# platine_clairage_voiture.net
KiCad netlist of a schematic drawn in EAGLE
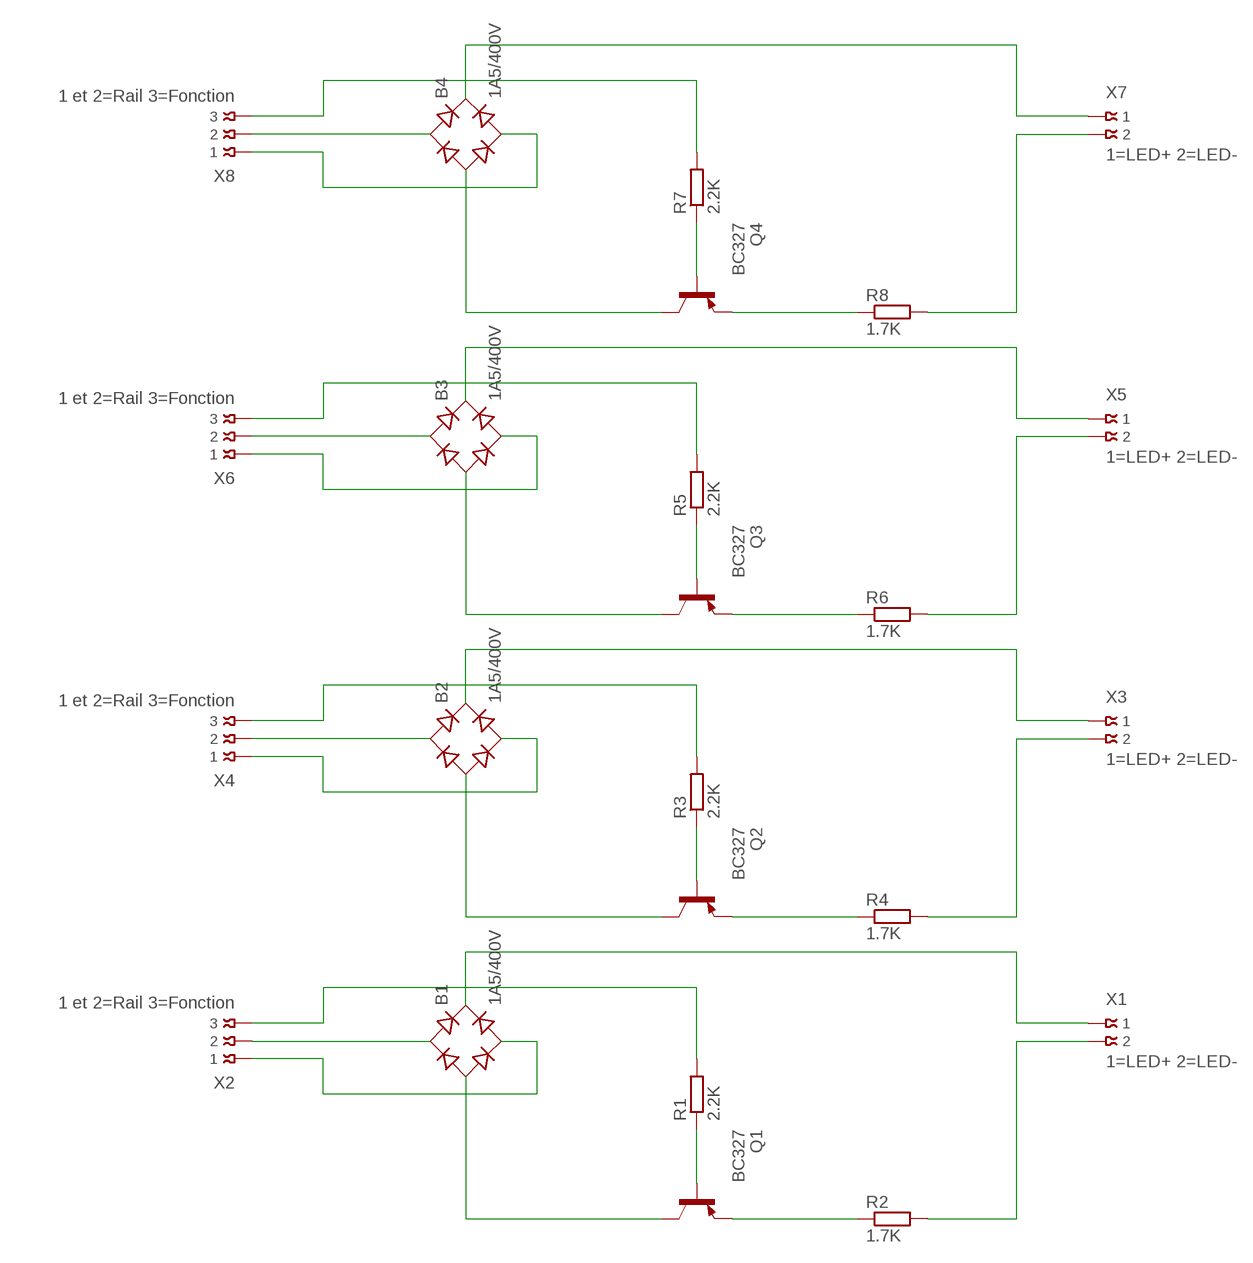
[diagram p0: schematic, sheet 1]

(export (version "E")
  (design (tool "Eeschema 10.0.6"))
  (components
    (comp (ref "B1")
      (value "1A5/400V")
      (footprint "eagle-import:RB1A")
      (libsource (lib "eagle-import") (part "RECTIFIER-RB1A"))
    )
    (comp (ref "B2")
      (value "1A5/400V")
      (footprint "eagle-import:RB1A")
      (libsource (lib "eagle-import") (part "RECTIFIER-RB1A"))
    )
    (comp (ref "B3")
      (value "1A5/400V")
      (footprint "eagle-import:RB1A")
      (libsource (lib "eagle-import") (part "RECTIFIER-RB1A"))
    )
    (comp (ref "B4")
      (value "1A5/400V")
      (footprint "eagle-import:RB1A")
      (libsource (lib "eagle-import") (part "RECTIFIER-RB1A"))
    )
    (comp (ref "Q1")
      (value "BC327")
      (footprint "eagle-import:TO92-EBC")
      (libsource (lib "eagle-import") (part "BC327"))
    )
    (comp (ref "Q2")
      (value "BC327")
      (footprint "eagle-import:TO92-EBC")
      (libsource (lib "eagle-import") (part "BC327"))
    )
    (comp (ref "Q3")
      (value "BC327")
      (footprint "eagle-import:TO92-EBC")
      (libsource (lib "eagle-import") (part "BC327"))
    )
    (comp (ref "Q4")
      (value "BC327")
      (footprint "eagle-import:TO92-EBC")
      (libsource (lib "eagle-import") (part "BC327"))
    )
    (comp (ref "R1")
      (value "2.2K")
      (footprint "eagle-import:0207_10")
      (libsource (lib "eagle-import") (part "R-EU_0207/10"))
    )
    (comp (ref "R2")
      (value "1.7K")
      (footprint "eagle-import:0207_10")
      (libsource (lib "eagle-import") (part "R-EU_0207/10"))
    )
    (comp (ref "R3")
      (value "2.2K")
      (footprint "eagle-import:0207_10")
      (libsource (lib "eagle-import") (part "R-EU_0207/10"))
    )
    (comp (ref "R4")
      (value "1.7K")
      (footprint "eagle-import:0207_10")
      (libsource (lib "eagle-import") (part "R-EU_0207/10"))
    )
    (comp (ref "R5")
      (value "2.2K")
      (footprint "eagle-import:0207_10")
      (libsource (lib "eagle-import") (part "R-EU_0207/10"))
    )
    (comp (ref "R6")
      (value "1.7K")
      (footprint "eagle-import:0207_10")
      (libsource (lib "eagle-import") (part "R-EU_0207/10"))
    )
    (comp (ref "R7")
      (value "2.2K")
      (footprint "eagle-import:0207_10")
      (libsource (lib "eagle-import") (part "R-EU_0207/10"))
    )
    (comp (ref "R8")
      (value "1.7K")
      (footprint "eagle-import:0207_10")
      (libsource (lib "eagle-import") (part "R-EU_0207/10"))
    )
    (comp (ref "X1")
      (value "1=LED+ 2=LED-")
      (footprint "eagle-import:009176002")
      (fields (field (name "MPN") "009176002001006"))
      (libsource (lib "eagle-import") (part "00917?0026"))
    )
    (comp (ref "X2")
      (value "1 et 2=Rail 3=Fonction")
      (footprint "eagle-import:009176003")
      (fields (field (name "MPN") "009176003001106"))
      (libsource (lib "eagle-import") (part "00917?0036"))
    )
    (comp (ref "X3")
      (value "1=LED+ 2=LED-")
      (footprint "eagle-import:009176002")
      (fields (field (name "MPN") "009176002001006"))
      (libsource (lib "eagle-import") (part "00917?0026"))
    )
    (comp (ref "X4")
      (value "1 et 2=Rail 3=Fonction")
      (footprint "eagle-import:009176003")
      (fields (field (name "MPN") "009176003001106"))
      (libsource (lib "eagle-import") (part "00917?0036"))
    )
    (comp (ref "X5")
      (value "1=LED+ 2=LED-")
      (footprint "eagle-import:009176002")
      (fields (field (name "MPN") "009176002001006"))
      (libsource (lib "eagle-import") (part "00917?0026"))
    )
    (comp (ref "X6")
      (value "1 et 2=Rail 3=Fonction")
      (footprint "eagle-import:009176003")
      (fields (field (name "MPN") "009176003001106"))
      (libsource (lib "eagle-import") (part "00917?0036"))
    )
    (comp (ref "X7")
      (value "1=LED+ 2=LED-")
      (footprint "eagle-import:009176002")
      (fields (field (name "MPN") "009176002001006"))
      (libsource (lib "eagle-import") (part "00917?0026"))
    )
    (comp (ref "X8")
      (value "1 et 2=Rail 3=Fonction")
      (footprint "eagle-import:009176003")
      (fields (field (name "MPN") "009176003001106"))
      (libsource (lib "eagle-import") (part "00917?0036"))
    )
  )
  (nets
    (net (code "1") (name "Net-(B1-Pad+)") (class "Default")
      (node (ref "B1") (pin "+") (pinfunction "+_+") (pintype "passive"))
      (node (ref "X1") (pin "1") (pinfunction "1_1") (pintype "passive"))
    )
    (net (code "2") (name "Net-(B1-Pad-)") (class "Default")
      (node (ref "B1") (pin "-") (pinfunction "-_-") (pintype "passive"))
      (node (ref "Q1") (pin "C") (pinfunction "C_C") (pintype "passive"))
    )
    (net (code "3") (name "Net-(B1-PadAC1)") (class "Default")
      (node (ref "B1") (pin "AC1") (pinfunction "AC1_AC1") (pintype "passive"))
      (node (ref "X2") (pin "2") (pinfunction "2_2") (pintype "passive"))
    )
    (net (code "4") (name "Net-(B1-PadAC2)") (class "Default")
      (node (ref "B1") (pin "AC2") (pinfunction "AC2_AC2") (pintype "passive"))
      (node (ref "X2") (pin "1") (pinfunction "1_1") (pintype "passive"))
    )
    (net (code "5") (name "Net-(B2-Pad+)") (class "Default")
      (node (ref "B2") (pin "+") (pinfunction "+_+") (pintype "passive"))
      (node (ref "X3") (pin "1") (pinfunction "1_1") (pintype "passive"))
    )
    (net (code "6") (name "Net-(B2-Pad-)") (class "Default")
      (node (ref "B2") (pin "-") (pinfunction "-_-") (pintype "passive"))
      (node (ref "Q2") (pin "C") (pinfunction "C_C") (pintype "passive"))
    )
    (net (code "7") (name "Net-(B2-PadAC1)") (class "Default")
      (node (ref "B2") (pin "AC1") (pinfunction "AC1_AC1") (pintype "passive"))
      (node (ref "X4") (pin "2") (pinfunction "2_2") (pintype "passive"))
    )
    (net (code "8") (name "Net-(B2-PadAC2)") (class "Default")
      (node (ref "B2") (pin "AC2") (pinfunction "AC2_AC2") (pintype "passive"))
      (node (ref "X4") (pin "1") (pinfunction "1_1") (pintype "passive"))
    )
    (net (code "9") (name "Net-(B3-Pad+)") (class "Default")
      (node (ref "B3") (pin "+") (pinfunction "+_+") (pintype "passive"))
      (node (ref "X5") (pin "1") (pinfunction "1_1") (pintype "passive"))
    )
    (net (code "10") (name "Net-(B3-Pad-)") (class "Default")
      (node (ref "B3") (pin "-") (pinfunction "-_-") (pintype "passive"))
      (node (ref "Q3") (pin "C") (pinfunction "C_C") (pintype "passive"))
    )
    (net (code "11") (name "Net-(B3-PadAC1)") (class "Default")
      (node (ref "B3") (pin "AC1") (pinfunction "AC1_AC1") (pintype "passive"))
      (node (ref "X6") (pin "2") (pinfunction "2_2") (pintype "passive"))
    )
    (net (code "12") (name "Net-(B3-PadAC2)") (class "Default")
      (node (ref "B3") (pin "AC2") (pinfunction "AC2_AC2") (pintype "passive"))
      (node (ref "X6") (pin "1") (pinfunction "1_1") (pintype "passive"))
    )
    (net (code "13") (name "Net-(B4-Pad+)") (class "Default")
      (node (ref "B4") (pin "+") (pinfunction "+_+") (pintype "passive"))
      (node (ref "X7") (pin "1") (pinfunction "1_1") (pintype "passive"))
    )
    (net (code "14") (name "Net-(B4-Pad-)") (class "Default")
      (node (ref "B4") (pin "-") (pinfunction "-_-") (pintype "passive"))
      (node (ref "Q4") (pin "C") (pinfunction "C_C") (pintype "passive"))
    )
    (net (code "15") (name "Net-(B4-PadAC1)") (class "Default")
      (node (ref "B4") (pin "AC1") (pinfunction "AC1_AC1") (pintype "passive"))
      (node (ref "X8") (pin "2") (pinfunction "2_2") (pintype "passive"))
    )
    (net (code "16") (name "Net-(B4-PadAC2)") (class "Default")
      (node (ref "B4") (pin "AC2") (pinfunction "AC2_AC2") (pintype "passive"))
      (node (ref "X8") (pin "1") (pinfunction "1_1") (pintype "passive"))
    )
    (net (code "17") (name "Net-(Q1-PadB)") (class "Default")
      (node (ref "Q1") (pin "B") (pinfunction "B_B") (pintype "passive"))
      (node (ref "R1") (pin "1") (pinfunction "1_1") (pintype "passive"))
    )
    (net (code "18") (name "Net-(Q1-PadE)") (class "Default")
      (node (ref "Q1") (pin "E") (pinfunction "E_E") (pintype "passive"))
      (node (ref "R2") (pin "1") (pinfunction "1_1") (pintype "passive"))
    )
    (net (code "19") (name "Net-(Q2-PadB)") (class "Default")
      (node (ref "Q2") (pin "B") (pinfunction "B_B") (pintype "passive"))
      (node (ref "R3") (pin "1") (pinfunction "1_1") (pintype "passive"))
    )
    (net (code "20") (name "Net-(Q2-PadE)") (class "Default")
      (node (ref "Q2") (pin "E") (pinfunction "E_E") (pintype "passive"))
      (node (ref "R4") (pin "1") (pinfunction "1_1") (pintype "passive"))
    )
    (net (code "21") (name "Net-(Q3-PadB)") (class "Default")
      (node (ref "Q3") (pin "B") (pinfunction "B_B") (pintype "passive"))
      (node (ref "R5") (pin "1") (pinfunction "1_1") (pintype "passive"))
    )
    (net (code "22") (name "Net-(Q3-PadE)") (class "Default")
      (node (ref "Q3") (pin "E") (pinfunction "E_E") (pintype "passive"))
      (node (ref "R6") (pin "1") (pinfunction "1_1") (pintype "passive"))
    )
    (net (code "23") (name "Net-(Q4-PadB)") (class "Default")
      (node (ref "Q4") (pin "B") (pinfunction "B_B") (pintype "passive"))
      (node (ref "R7") (pin "1") (pinfunction "1_1") (pintype "passive"))
    )
    (net (code "24") (name "Net-(Q4-PadE)") (class "Default")
      (node (ref "Q4") (pin "E") (pinfunction "E_E") (pintype "passive"))
      (node (ref "R8") (pin "1") (pinfunction "1_1") (pintype "passive"))
    )
    (net (code "25") (name "Net-(R1-Pad2)") (class "Default")
      (node (ref "R1") (pin "2") (pinfunction "2_2") (pintype "passive"))
      (node (ref "X2") (pin "3") (pinfunction "3_3") (pintype "passive"))
    )
    (net (code "26") (name "Net-(R2-Pad2)") (class "Default")
      (node (ref "R2") (pin "2") (pinfunction "2_2") (pintype "passive"))
      (node (ref "X1") (pin "2") (pinfunction "2_2") (pintype "passive"))
    )
    (net (code "27") (name "Net-(R3-Pad2)") (class "Default")
      (node (ref "R3") (pin "2") (pinfunction "2_2") (pintype "passive"))
      (node (ref "X4") (pin "3") (pinfunction "3_3") (pintype "passive"))
    )
    (net (code "28") (name "Net-(R4-Pad2)") (class "Default")
      (node (ref "R4") (pin "2") (pinfunction "2_2") (pintype "passive"))
      (node (ref "X3") (pin "2") (pinfunction "2_2") (pintype "passive"))
    )
    (net (code "29") (name "Net-(R5-Pad2)") (class "Default")
      (node (ref "R5") (pin "2") (pinfunction "2_2") (pintype "passive"))
      (node (ref "X6") (pin "3") (pinfunction "3_3") (pintype "passive"))
    )
    (net (code "30") (name "Net-(R6-Pad2)") (class "Default")
      (node (ref "R6") (pin "2") (pinfunction "2_2") (pintype "passive"))
      (node (ref "X5") (pin "2") (pinfunction "2_2") (pintype "passive"))
    )
    (net (code "31") (name "Net-(R7-Pad2)") (class "Default")
      (node (ref "R7") (pin "2") (pinfunction "2_2") (pintype "passive"))
      (node (ref "X8") (pin "3") (pinfunction "3_3") (pintype "passive"))
    )
    (net (code "32") (name "Net-(R8-Pad2)") (class "Default")
      (node (ref "R8") (pin "2") (pinfunction "2_2") (pintype "passive"))
      (node (ref "X7") (pin "2") (pinfunction "2_2") (pintype "passive"))
    )
  )
)
